# adn_Lego.net
KiCad netlist of a schematic drawn in EAGLE
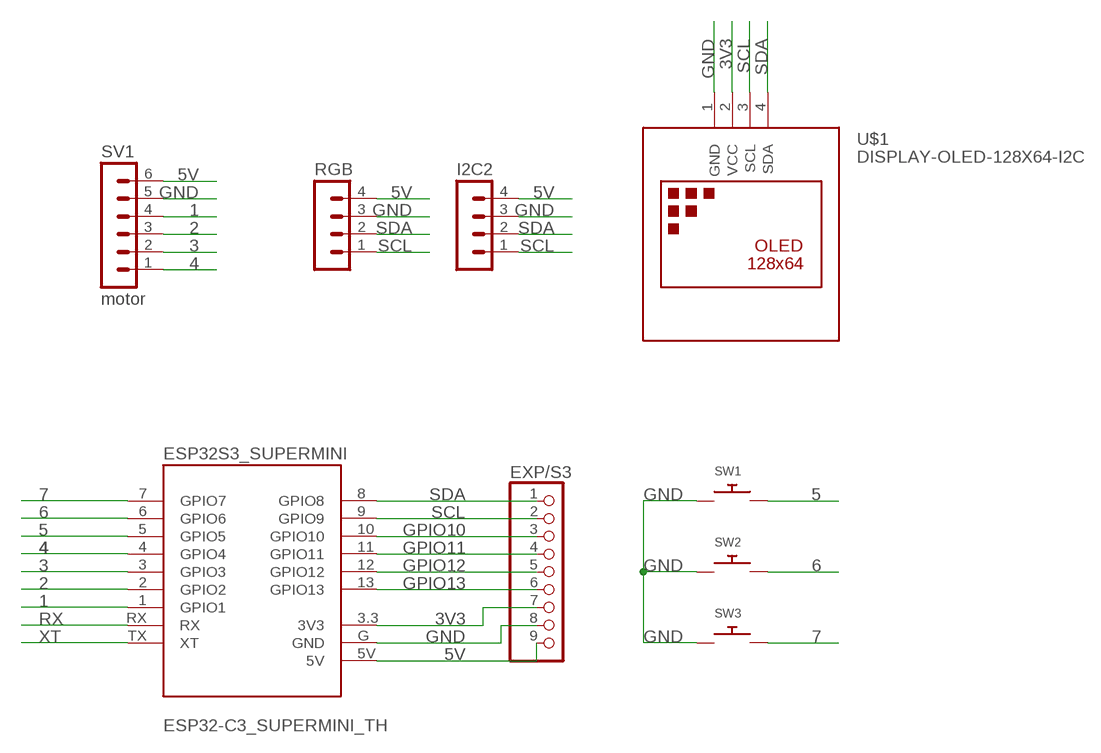
[diagram p0: schematic, sheet 1]

(export (version "E")
  (design (tool "Eeschema 10.0.6"))
  (components
    (comp (ref "ESP32S3_SUPERMINI")
      (value "ESP32-C3_SUPERMINI_TH")
      (footprint "eagle-import:MODULE_ESP32-C3_SUPERMINI_TH")
      (fields (field (name "MF") "Espressif Systems") (field (name "MP") "ESP32-S3 SuperMini_TH"))
      (libsource (lib "eagle-import") (part "ESP32-C3_SUPERMINI_TH"))
    )
    (comp (ref "EXP/S3")
      (value "PINHD-1X9")
      (footprint "eagle-import:1X09")
      (libsource (lib "eagle-import") (part "PINHD-1X9"))
    )
    (comp (ref "I2C2")
      (value "MA04-1")
      (footprint "eagle-import:MA04-1")
      (libsource (lib "eagle-import") (part "MA04-1"))
    )
    (comp (ref "RGB")
      (value "MA04-1")
      (footprint "eagle-import:MA04-1")
      (libsource (lib "eagle-import") (part "MA04-1"))
    )
    (comp (ref "SV1")
      (value "motor")
      (footprint "eagle-import:MA06-1")
      (libsource (lib "eagle-import") (part "MA06-1"))
    )
    (comp (ref "SW1")
      (value "SWITCH_PUSHBUTTONEVQ-PE")
      (footprint "eagle-import:TACT_PANA-EVQ")
      (libsource (lib "eagle-import") (part "SWITCH_PUSHBUTTONEVQ-PE"))
    )
    (comp (ref "SW2")
      (value "SWITCH_PUSHBUTTONEVQ-PE")
      (footprint "eagle-import:TACT_PANA-EVQ")
      (libsource (lib "eagle-import") (part "SWITCH_PUSHBUTTONEVQ-PE"))
    )
    (comp (ref "SW3")
      (value "SWITCH_PUSHBUTTONEVQ-PE")
      (footprint "eagle-import:TACT_PANA-EVQ")
      (libsource (lib "eagle-import") (part "SWITCH_PUSHBUTTONEVQ-PE"))
    )
    (comp (ref "U$1")
      (value "DISPLAY-OLED-128X64-I2C")
      (footprint "eagle-import:DISPLAY-OLED-128X64-I2C")
      (libsource (lib "eagle-import") (part "DISPLAY-OLED-128X64-I2C"))
    )
  )
  (nets
    (net (code "1") (name "/1") (class "Default")
      (node (ref "ESP32S3_SUPERMINI") (pin "1") (pinfunction "GPIO1_1") (pintype "bidirectional"))
      (node (ref "SV1") (pin "4") (pinfunction "4_4") (pintype "passive"))
    )
    (net (code "2") (name "/2") (class "Default")
      (node (ref "ESP32S3_SUPERMINI") (pin "2") (pinfunction "GPIO2_2") (pintype "bidirectional"))
      (node (ref "SV1") (pin "3") (pinfunction "3_3") (pintype "passive"))
    )
    (net (code "3") (name "/3") (class "Default")
      (node (ref "ESP32S3_SUPERMINI") (pin "3") (pinfunction "GPIO3_3") (pintype "bidirectional"))
      (node (ref "SV1") (pin "2") (pinfunction "2_2") (pintype "passive"))
    )
    (net (code "4") (name "/3V3") (class "Default")
      (node (ref "ESP32S3_SUPERMINI") (pin "3.3") (pinfunction "3V3_3.3") (pintype "power_in"))
      (node (ref "EXP/S3") (pin "7") (pinfunction "7_7") (pintype "passive"))
      (node (ref "U$1") (pin "2") (pinfunction "VCC_2") (pintype "power_in"))
    )
    (net (code "5") (name "/4") (class "Default")
      (node (ref "ESP32S3_SUPERMINI") (pin "4") (pinfunction "GPIO4_4") (pintype "bidirectional"))
      (node (ref "SV1") (pin "1") (pinfunction "1_1") (pintype "passive"))
    )
    (net (code "6") (name "/5") (class "Default")
      (node (ref "ESP32S3_SUPERMINI") (pin "5") (pinfunction "GPIO5_5") (pintype "bidirectional"))
      (node (ref "SW1") (pin "P$2") (pinfunction "P$2_P$2") (pintype "passive"))
    )
    (net (code "7") (name "/5V") (class "Default")
      (node (ref "ESP32S3_SUPERMINI") (pin "5V") (pinfunction "5V_5V") (pintype "power_in"))
      (node (ref "EXP/S3") (pin "9") (pinfunction "9_9") (pintype "passive"))
      (node (ref "I2C2") (pin "4") (pinfunction "4_4") (pintype "passive"))
      (node (ref "RGB") (pin "4") (pinfunction "4_4") (pintype "passive"))
      (node (ref "SV1") (pin "6") (pinfunction "6_6") (pintype "passive"))
    )
    (net (code "8") (name "/6") (class "Default")
      (node (ref "ESP32S3_SUPERMINI") (pin "6") (pinfunction "GPIO6_6") (pintype "bidirectional"))
      (node (ref "SW2") (pin "P$2") (pinfunction "P$2_P$2") (pintype "passive"))
    )
    (net (code "9") (name "/7") (class "Default")
      (node (ref "ESP32S3_SUPERMINI") (pin "7") (pinfunction "GPIO7_7") (pintype "bidirectional"))
      (node (ref "SW3") (pin "P$2") (pinfunction "P$2_P$2") (pintype "passive"))
    )
    (net (code "10") (name "/GND") (class "Default")
      (node (ref "ESP32S3_SUPERMINI") (pin "G") (pinfunction "GND_G") (pintype "power_in"))
      (node (ref "EXP/S3") (pin "8") (pinfunction "8_8") (pintype "passive"))
      (node (ref "I2C2") (pin "3") (pinfunction "3_3") (pintype "passive"))
      (node (ref "RGB") (pin "3") (pinfunction "3_3") (pintype "passive"))
      (node (ref "SV1") (pin "5") (pinfunction "5_5") (pintype "passive"))
      (node (ref "SW1") (pin "P$1") (pinfunction "P$1_P$1") (pintype "passive"))
      (node (ref "SW2") (pin "P$1") (pinfunction "P$1_P$1") (pintype "passive"))
      (node (ref "SW3") (pin "P$1") (pinfunction "P$1_P$1") (pintype "passive"))
      (node (ref "U$1") (pin "1") (pinfunction "GND_1") (pintype "power_in"))
    )
    (net (code "11") (name "/GPIO10") (class "Default")
      (node (ref "ESP32S3_SUPERMINI") (pin "10") (pinfunction "GPIO10_10") (pintype "bidirectional"))
      (node (ref "EXP/S3") (pin "3") (pinfunction "3_3") (pintype "passive"))
    )
    (net (code "12") (name "/GPIO11") (class "Default")
      (node (ref "ESP32S3_SUPERMINI") (pin "11") (pinfunction "GPIO11_11") (pintype "bidirectional"))
      (node (ref "EXP/S3") (pin "4") (pinfunction "4_4") (pintype "passive"))
    )
    (net (code "13") (name "/GPIO12") (class "Default")
      (node (ref "ESP32S3_SUPERMINI") (pin "12") (pinfunction "GPIO12_12") (pintype "bidirectional"))
      (node (ref "EXP/S3") (pin "5") (pinfunction "5_5") (pintype "passive"))
    )
    (net (code "14") (name "/GPIO13") (class "Default")
      (node (ref "ESP32S3_SUPERMINI") (pin "13") (pinfunction "GPIO13_13") (pintype "bidirectional"))
      (node (ref "EXP/S3") (pin "6") (pinfunction "6_6") (pintype "passive"))
    )
    (net (code "15") (name "/RX") (class "Default")
      (node (ref "ESP32S3_SUPERMINI") (pin "RX") (pinfunction "RX_RX") (pintype "bidirectional"))
    )
    (net (code "16") (name "/SCL") (class "Default")
      (node (ref "ESP32S3_SUPERMINI") (pin "9") (pinfunction "GPIO9_9") (pintype "bidirectional"))
      (node (ref "EXP/S3") (pin "2") (pinfunction "2_2") (pintype "passive"))
      (node (ref "I2C2") (pin "1") (pinfunction "1_1") (pintype "passive"))
      (node (ref "RGB") (pin "1") (pinfunction "1_1") (pintype "passive"))
      (node (ref "U$1") (pin "3") (pinfunction "SCL_3") (pintype "bidirectional"))
    )
    (net (code "17") (name "/SDA") (class "Default")
      (node (ref "ESP32S3_SUPERMINI") (pin "8") (pinfunction "GPIO8_8") (pintype "bidirectional"))
      (node (ref "EXP/S3") (pin "1") (pinfunction "1_1") (pintype "passive"))
      (node (ref "I2C2") (pin "2") (pinfunction "2_2") (pintype "passive"))
      (node (ref "RGB") (pin "2") (pinfunction "2_2") (pintype "passive"))
      (node (ref "U$1") (pin "4") (pinfunction "SDA_4") (pintype "bidirectional"))
    )
    (net (code "18") (name "/XT") (class "Default")
      (node (ref "ESP32S3_SUPERMINI") (pin "TX") (pinfunction "XT_TX") (pintype "bidirectional"))
    )
  )
)
